# dashboard_2.net
KiCad netlist of a schematic drawn in EAGLE
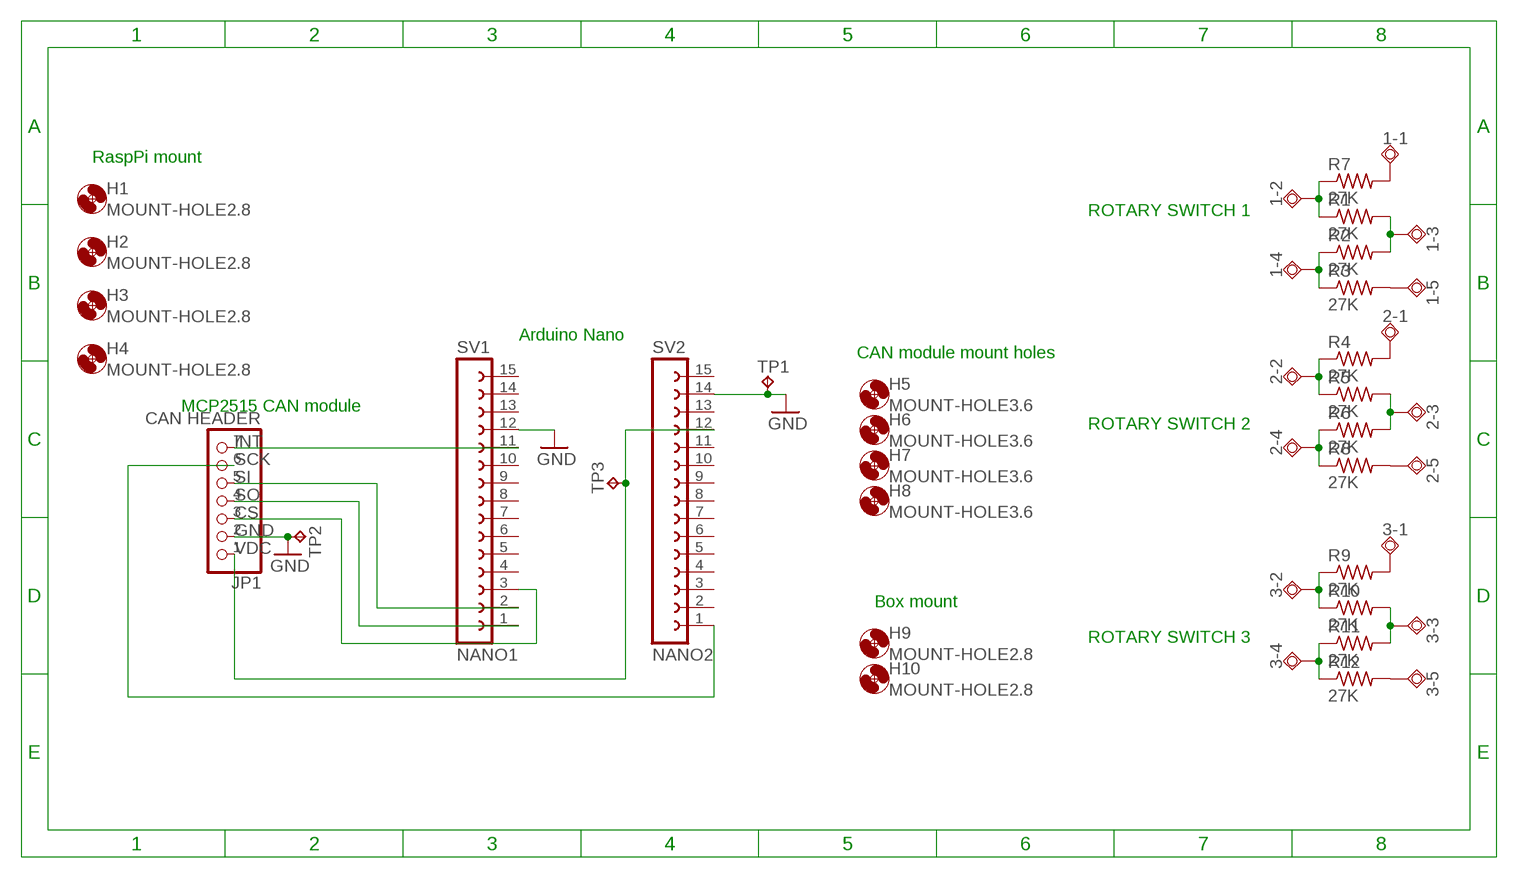
[diagram p0: schematic, sheet 1]

(export (version "E")
  (design (tool "Eeschema 10.0.6"))
  (components
    (comp (ref "1-1")
      (value "TPSQPAD1-13Y")
      (footprint "eagle-import:P1-13Y")
      (libsource (lib "eagle-import") (part "TPSQPAD1-13Y"))
    )
    (comp (ref "1-2")
      (value "TPSQPAD1-13")
      (footprint "eagle-import:P1-13")
      (libsource (lib "eagle-import") (part "TPSQPAD1-13"))
    )
    (comp (ref "1-3")
      (value "TPSQPAD1-13")
      (footprint "eagle-import:P1-13")
      (libsource (lib "eagle-import") (part "TPSQPAD1-13"))
    )
    (comp (ref "1-4")
      (value "TPSQPAD1-13")
      (footprint "eagle-import:P1-13")
      (libsource (lib "eagle-import") (part "TPSQPAD1-13"))
    )
    (comp (ref "1-5")
      (value "TPSQPAD1-13Y")
      (footprint "eagle-import:P1-13Y")
      (libsource (lib "eagle-import") (part "TPSQPAD1-13Y"))
    )
    (comp (ref "2-1")
      (value "TPSQPAD1-13Y")
      (footprint "eagle-import:P1-13Y")
      (libsource (lib "eagle-import") (part "TPSQPAD1-13Y"))
    )
    (comp (ref "2-2")
      (value "TPSQPAD1-13")
      (footprint "eagle-import:P1-13")
      (libsource (lib "eagle-import") (part "TPSQPAD1-13"))
    )
    (comp (ref "2-3")
      (value "TPSQPAD1-13")
      (footprint "eagle-import:P1-13")
      (libsource (lib "eagle-import") (part "TPSQPAD1-13"))
    )
    (comp (ref "2-4")
      (value "TPSQPAD1-13")
      (footprint "eagle-import:P1-13")
      (libsource (lib "eagle-import") (part "TPSQPAD1-13"))
    )
    (comp (ref "2-5")
      (value "TPSQPAD1-13Y")
      (footprint "eagle-import:P1-13Y")
      (libsource (lib "eagle-import") (part "TPSQPAD1-13Y"))
    )
    (comp (ref "3-1")
      (value "TPSQPAD1-13Y")
      (footprint "eagle-import:P1-13Y")
      (libsource (lib "eagle-import") (part "TPSQPAD1-13Y"))
    )
    (comp (ref "3-2")
      (value "TPSQPAD1-13")
      (footprint "eagle-import:P1-13")
      (libsource (lib "eagle-import") (part "TPSQPAD1-13"))
    )
    (comp (ref "3-3")
      (value "TPSQPAD1-13")
      (footprint "eagle-import:P1-13")
      (libsource (lib "eagle-import") (part "TPSQPAD1-13"))
    )
    (comp (ref "3-4")
      (value "TPSQPAD1-13")
      (footprint "eagle-import:P1-13")
      (libsource (lib "eagle-import") (part "TPSQPAD1-13"))
    )
    (comp (ref "3-5")
      (value "TPSQPAD1-13Y")
      (footprint "eagle-import:P1-13Y")
      (libsource (lib "eagle-import") (part "TPSQPAD1-13Y"))
    )
    (comp (ref "H1")
      (value "MOUNT-HOLE2.8")
      (footprint "eagle-import:2,8")
      (libsource (lib "eagle-import") (part "MOUNT-HOLE2.8"))
    )
    (comp (ref "H2")
      (value "MOUNT-HOLE2.8")
      (footprint "eagle-import:2,8")
      (libsource (lib "eagle-import") (part "MOUNT-HOLE2.8"))
    )
    (comp (ref "H3")
      (value "MOUNT-HOLE2.8")
      (footprint "eagle-import:2,8")
      (libsource (lib "eagle-import") (part "MOUNT-HOLE2.8"))
    )
    (comp (ref "H4")
      (value "MOUNT-HOLE2.8")
      (footprint "eagle-import:2,8")
      (libsource (lib "eagle-import") (part "MOUNT-HOLE2.8"))
    )
    (comp (ref "H5")
      (value "MOUNT-HOLE3.6")
      (footprint "eagle-import:3,6")
      (libsource (lib "eagle-import") (part "MOUNT-HOLE3.6"))
    )
    (comp (ref "H6")
      (value "MOUNT-HOLE3.6")
      (footprint "eagle-import:3,6")
      (libsource (lib "eagle-import") (part "MOUNT-HOLE3.6"))
    )
    (comp (ref "H7")
      (value "MOUNT-HOLE3.6")
      (footprint "eagle-import:3,6")
      (libsource (lib "eagle-import") (part "MOUNT-HOLE3.6"))
    )
    (comp (ref "H8")
      (value "MOUNT-HOLE3.6")
      (footprint "eagle-import:3,6")
      (libsource (lib "eagle-import") (part "MOUNT-HOLE3.6"))
    )
    (comp (ref "H9")
      (value "MOUNT-HOLE2.8")
      (footprint "eagle-import:2,8")
      (libsource (lib "eagle-import") (part "MOUNT-HOLE2.8"))
    )
    (comp (ref "H10")
      (value "MOUNT-HOLE2.8")
      (footprint "eagle-import:2,8")
      (libsource (lib "eagle-import") (part "MOUNT-HOLE2.8"))
    )
    (comp (ref "JP1")
      (value "CAN HEADER")
      (footprint "eagle-import:1X07M")
      (libsource (lib "eagle-import") (part "PINHD-1X7M"))
    )
    (comp (ref "R1")
      (value "27K")
      (footprint "eagle-import:0309_10")
      (libsource (lib "eagle-import") (part "R-US_0309/10"))
    )
    (comp (ref "R2")
      (value "27K")
      (footprint "eagle-import:0309_10")
      (libsource (lib "eagle-import") (part "R-US_0309/10"))
    )
    (comp (ref "R3")
      (value "27K")
      (footprint "eagle-import:0309_10")
      (libsource (lib "eagle-import") (part "R-US_0309/10"))
    )
    (comp (ref "R4")
      (value "27K")
      (footprint "eagle-import:0309_10")
      (libsource (lib "eagle-import") (part "R-US_0309/10"))
    )
    (comp (ref "R5")
      (value "27K")
      (footprint "eagle-import:0309_10")
      (libsource (lib "eagle-import") (part "R-US_0309/10"))
    )
    (comp (ref "R6")
      (value "27K")
      (footprint "eagle-import:0309_10")
      (libsource (lib "eagle-import") (part "R-US_0309/10"))
    )
    (comp (ref "R7")
      (value "27K")
      (footprint "eagle-import:0309_10")
      (libsource (lib "eagle-import") (part "R-US_0309/10"))
    )
    (comp (ref "R8")
      (value "27K")
      (footprint "eagle-import:0309_10")
      (libsource (lib "eagle-import") (part "R-US_0309/10"))
    )
    (comp (ref "R9")
      (value "27K")
      (footprint "eagle-import:0309_10")
      (libsource (lib "eagle-import") (part "R-US_0309/10"))
    )
    (comp (ref "R10")
      (value "27K")
      (footprint "eagle-import:0309_10")
      (libsource (lib "eagle-import") (part "R-US_0309/10"))
    )
    (comp (ref "R11")
      (value "27K")
      (footprint "eagle-import:0309_10")
      (libsource (lib "eagle-import") (part "R-US_0309/10"))
    )
    (comp (ref "R12")
      (value "27K")
      (footprint "eagle-import:0309_10")
      (libsource (lib "eagle-import") (part "R-US_0309/10"))
    )
    (comp (ref "SV1")
      (value "NANO1")
      (footprint "eagle-import:FE15")
      (libsource (lib "eagle-import") (part "FE15-1"))
    )
    (comp (ref "SV2")
      (value "NANO2")
      (footprint "eagle-import:FE15")
      (libsource (lib "eagle-import") (part "FE15-1"))
    )
    (comp (ref "TP1")
      (value "TPTP20SQ")
      (footprint "eagle-import:TP20SQ")
      (libsource (lib "eagle-import") (part "TPTP20SQ"))
    )
    (comp (ref "TP2")
      (value "TPTP20SQ")
      (footprint "eagle-import:TP20SQ")
      (libsource (lib "eagle-import") (part "TPTP20SQ"))
    )
    (comp (ref "TP3")
      (value "TPTP20SQ")
      (footprint "eagle-import:TP20SQ")
      (libsource (lib "eagle-import") (part "TPTP20SQ"))
    )
  )
  (nets
    (net (code "1") (name "/CS") (class "Default")
      (node (ref "JP1") (pin "3") (pinfunction "3_3") (pintype "passive"))
      (node (ref "SV1") (pin "3") (pinfunction "3_3") (pintype "passive"))
    )
    (net (code "2") (name "/INT") (class "Default")
      (node (ref "JP1") (pin "7") (pinfunction "7_7") (pintype "passive"))
      (node (ref "SV1") (pin "11") (pinfunction "11_11") (pintype "passive"))
    )
    (net (code "3") (name "/SCK") (class "Default")
      (node (ref "JP1") (pin "6") (pinfunction "6_6") (pintype "passive"))
      (node (ref "SV2") (pin "1") (pinfunction "1_1") (pintype "passive"))
    )
    (net (code "4") (name "/SI") (class "Default")
      (node (ref "JP1") (pin "5") (pinfunction "5_5") (pintype "passive"))
      (node (ref "SV1") (pin "2") (pinfunction "2_2") (pintype "passive"))
    )
    (net (code "5") (name "/SO") (class "Default")
      (node (ref "JP1") (pin "4") (pinfunction "4_4") (pintype "passive"))
      (node (ref "SV1") (pin "1") (pinfunction "1_1") (pintype "passive"))
    )
    (net (code "6") (name "/VDC") (class "Default")
      (node (ref "JP1") (pin "1") (pinfunction "1_1") (pintype "passive"))
      (node (ref "SV2") (pin "12") (pinfunction "12_12") (pintype "passive"))
      (node (ref "TP3") (pin "TP") (pinfunction "TP_TP") (pintype "input"))
    )
    (net (code "7") (name "GND") (class "Default")
      (node (ref "JP1") (pin "2") (pinfunction "2_2") (pintype "passive"))
      (node (ref "SV1") (pin "12") (pinfunction "12_12") (pintype "passive"))
      (node (ref "SV2") (pin "14") (pinfunction "14_14") (pintype "passive"))
      (node (ref "TP1") (pin "TP") (pinfunction "TP_TP") (pintype "input"))
      (node (ref "TP2") (pin "TP") (pinfunction "TP_TP") (pintype "input"))
    )
    (net (code "8") (name "Net-(1-1-TP)") (class "Default")
      (node (ref "1-1") (pin "1") (pinfunction "TP_1") (pintype "input"))
      (node (ref "R7") (pin "2") (pinfunction "2_2") (pintype "passive"))
    )
    (net (code "9") (name "Net-(1-2-TP)") (class "Default")
      (node (ref "1-2") (pin "1") (pinfunction "TP_1") (pintype "input"))
      (node (ref "R1") (pin "1") (pinfunction "1_1") (pintype "passive"))
      (node (ref "R7") (pin "1") (pinfunction "1_1") (pintype "passive"))
    )
    (net (code "10") (name "Net-(1-3-TP)") (class "Default")
      (node (ref "1-3") (pin "1") (pinfunction "TP_1") (pintype "input"))
      (node (ref "R1") (pin "2") (pinfunction "2_2") (pintype "passive"))
      (node (ref "R2") (pin "2") (pinfunction "2_2") (pintype "passive"))
    )
    (net (code "11") (name "Net-(1-4-TP)") (class "Default")
      (node (ref "1-4") (pin "1") (pinfunction "TP_1") (pintype "input"))
      (node (ref "R2") (pin "1") (pinfunction "1_1") (pintype "passive"))
      (node (ref "R3") (pin "1") (pinfunction "1_1") (pintype "passive"))
    )
    (net (code "12") (name "Net-(1-5-TP)") (class "Default")
      (node (ref "1-5") (pin "1") (pinfunction "TP_1") (pintype "input"))
      (node (ref "R3") (pin "2") (pinfunction "2_2") (pintype "passive"))
    )
    (net (code "13") (name "Net-(2-1-TP)") (class "Default")
      (node (ref "2-1") (pin "1") (pinfunction "TP_1") (pintype "input"))
      (node (ref "R4") (pin "2") (pinfunction "2_2") (pintype "passive"))
    )
    (net (code "14") (name "Net-(2-2-TP)") (class "Default")
      (node (ref "2-2") (pin "1") (pinfunction "TP_1") (pintype "input"))
      (node (ref "R4") (pin "1") (pinfunction "1_1") (pintype "passive"))
      (node (ref "R5") (pin "1") (pinfunction "1_1") (pintype "passive"))
    )
    (net (code "15") (name "Net-(2-3-TP)") (class "Default")
      (node (ref "2-3") (pin "1") (pinfunction "TP_1") (pintype "input"))
      (node (ref "R5") (pin "2") (pinfunction "2_2") (pintype "passive"))
      (node (ref "R6") (pin "2") (pinfunction "2_2") (pintype "passive"))
    )
    (net (code "16") (name "Net-(2-4-TP)") (class "Default")
      (node (ref "2-4") (pin "1") (pinfunction "TP_1") (pintype "input"))
      (node (ref "R6") (pin "1") (pinfunction "1_1") (pintype "passive"))
      (node (ref "R8") (pin "1") (pinfunction "1_1") (pintype "passive"))
    )
    (net (code "17") (name "Net-(2-5-TP)") (class "Default")
      (node (ref "2-5") (pin "1") (pinfunction "TP_1") (pintype "input"))
      (node (ref "R8") (pin "2") (pinfunction "2_2") (pintype "passive"))
    )
    (net (code "18") (name "Net-(3-1-TP)") (class "Default")
      (node (ref "3-1") (pin "1") (pinfunction "TP_1") (pintype "input"))
      (node (ref "R9") (pin "2") (pinfunction "2_2") (pintype "passive"))
    )
    (net (code "19") (name "Net-(3-2-TP)") (class "Default")
      (node (ref "3-2") (pin "1") (pinfunction "TP_1") (pintype "input"))
      (node (ref "R10") (pin "1") (pinfunction "1_1") (pintype "passive"))
      (node (ref "R9") (pin "1") (pinfunction "1_1") (pintype "passive"))
    )
    (net (code "20") (name "Net-(3-3-TP)") (class "Default")
      (node (ref "3-3") (pin "1") (pinfunction "TP_1") (pintype "input"))
      (node (ref "R10") (pin "2") (pinfunction "2_2") (pintype "passive"))
      (node (ref "R11") (pin "2") (pinfunction "2_2") (pintype "passive"))
    )
    (net (code "21") (name "Net-(3-4-TP)") (class "Default")
      (node (ref "3-4") (pin "1") (pinfunction "TP_1") (pintype "input"))
      (node (ref "R11") (pin "1") (pinfunction "1_1") (pintype "passive"))
      (node (ref "R12") (pin "1") (pinfunction "1_1") (pintype "passive"))
    )
    (net (code "22") (name "Net-(3-5-TP)") (class "Default")
      (node (ref "3-5") (pin "1") (pinfunction "TP_1") (pintype "input"))
      (node (ref "R12") (pin "2") (pinfunction "2_2") (pintype "passive"))
    )
    (net (code "23") (name "unconnected-(SV1-Pad4)") (class "Default")
      (node (ref "SV1") (pin "4") (pinfunction "4_4") (pintype "passive"))
    )
    (net (code "24") (name "unconnected-(SV1-Pad5)") (class "Default")
      (node (ref "SV1") (pin "5") (pinfunction "5_5") (pintype "passive"))
    )
    (net (code "25") (name "unconnected-(SV1-Pad6)") (class "Default")
      (node (ref "SV1") (pin "6") (pinfunction "6_6") (pintype "passive"))
    )
    (net (code "26") (name "unconnected-(SV1-Pad7)") (class "Default")
      (node (ref "SV1") (pin "7") (pinfunction "7_7") (pintype "passive"))
    )
    (net (code "27") (name "unconnected-(SV1-Pad8)") (class "Default")
      (node (ref "SV1") (pin "8") (pinfunction "8_8") (pintype "passive"))
    )
    (net (code "28") (name "unconnected-(SV1-Pad9)") (class "Default")
      (node (ref "SV1") (pin "9") (pinfunction "9_9") (pintype "passive"))
    )
    (net (code "29") (name "unconnected-(SV1-Pad10)") (class "Default")
      (node (ref "SV1") (pin "10") (pinfunction "10_10") (pintype "passive"))
    )
    (net (code "30") (name "unconnected-(SV1-Pad13)") (class "Default")
      (node (ref "SV1") (pin "13") (pinfunction "13_13") (pintype "passive"))
    )
    (net (code "31") (name "unconnected-(SV1-Pad14)") (class "Default")
      (node (ref "SV1") (pin "14") (pinfunction "14_14") (pintype "passive"))
    )
    (net (code "32") (name "unconnected-(SV1-Pad15)") (class "Default")
      (node (ref "SV1") (pin "15") (pinfunction "15_15") (pintype "passive"))
    )
    (net (code "33") (name "unconnected-(SV2-Pad2)") (class "Default")
      (node (ref "SV2") (pin "2") (pinfunction "2_2") (pintype "passive"))
    )
    (net (code "34") (name "unconnected-(SV2-Pad3)") (class "Default")
      (node (ref "SV2") (pin "3") (pinfunction "3_3") (pintype "passive"))
    )
    (net (code "35") (name "unconnected-(SV2-Pad4)") (class "Default")
      (node (ref "SV2") (pin "4") (pinfunction "4_4") (pintype "passive"))
    )
    (net (code "36") (name "unconnected-(SV2-Pad5)") (class "Default")
      (node (ref "SV2") (pin "5") (pinfunction "5_5") (pintype "passive"))
    )
    (net (code "37") (name "unconnected-(SV2-Pad6)") (class "Default")
      (node (ref "SV2") (pin "6") (pinfunction "6_6") (pintype "passive"))
    )
    (net (code "38") (name "unconnected-(SV2-Pad7)") (class "Default")
      (node (ref "SV2") (pin "7") (pinfunction "7_7") (pintype "passive"))
    )
    (net (code "39") (name "unconnected-(SV2-Pad8)") (class "Default")
      (node (ref "SV2") (pin "8") (pinfunction "8_8") (pintype "passive"))
    )
    (net (code "40") (name "unconnected-(SV2-Pad9)") (class "Default")
      (node (ref "SV2") (pin "9") (pinfunction "9_9") (pintype "passive"))
    )
    (net (code "41") (name "unconnected-(SV2-Pad10)") (class "Default")
      (node (ref "SV2") (pin "10") (pinfunction "10_10") (pintype "passive"))
    )
    (net (code "42") (name "unconnected-(SV2-Pad11)") (class "Default")
      (node (ref "SV2") (pin "11") (pinfunction "11_11") (pintype "passive"))
    )
    (net (code "43") (name "unconnected-(SV2-Pad13)") (class "Default")
      (node (ref "SV2") (pin "13") (pinfunction "13_13") (pintype "passive"))
    )
    (net (code "44") (name "unconnected-(SV2-Pad15)") (class "Default")
      (node (ref "SV2") (pin "15") (pinfunction "15_15") (pintype "passive"))
    )
  )
)
